# TMP117.net
KiCad netlist of a schematic drawn in EAGLE
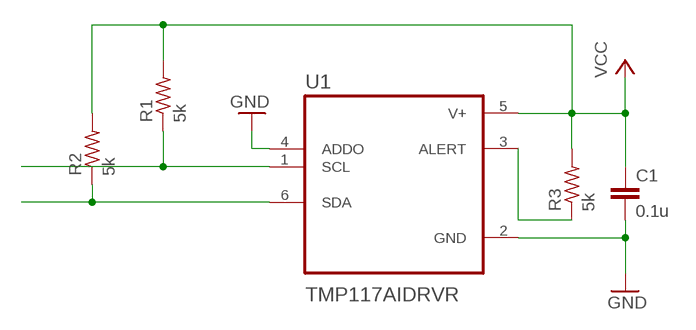
[diagram p0: schematic, sheet 1]

(export (version "E")
  (design (tool "Eeschema 10.0.6"))
  (components
    (comp (ref "C1")
      (value "0.1u")
      (footprint "eagle-import:C0402")
      (libsource (lib "eagle-import") (part "C-EUC0402"))
    )
    (comp (ref "R1")
      (value "5k")
      (footprint "eagle-import:R0402")
      (libsource (lib "eagle-import") (part "R-US_R0402"))
    )
    (comp (ref "R2")
      (value "5k")
      (footprint "eagle-import:R0402")
      (libsource (lib "eagle-import") (part "R-US_R0402"))
    )
    (comp (ref "R3")
      (value "5k")
      (footprint "eagle-import:R0402")
      (libsource (lib "eagle-import") (part "R-US_R0402"))
    )
    (comp (ref "U1")
      (value "TMP117AIDRVR")
      (footprint "eagle-import:SON65P200X200X80-7N")
      (fields (field (name "DIGI-KEY_PART_NUMBER") "296-51834-1-ND") (field (name "MF") "Texas Instruments"))
      (libsource (lib "eagle-import") (part "TMP117AIDRVR"))
    )
  )
  (nets
    (net (code "1") (name "GND") (class "Default")
      (node (ref "C1") (pin "2") (pinfunction "2_2") (pintype "passive"))
      (node (ref "U1") (pin "2") (pinfunction "GND_2") (pintype "power_in"))
      (node (ref "U1") (pin "4") (pinfunction "ADDO_4") (pintype "input"))
    )
    (net (code "2") (name "Net-(U1-ALERT)") (class "Default")
      (node (ref "R3") (pin "1") (pinfunction "1_1") (pintype "passive"))
      (node (ref "U1") (pin "3") (pinfunction "ALERT_3") (pintype "output"))
    )
    (net (code "3") (name "Net-(U1-SCL)") (class "Default")
      (node (ref "R1") (pin "1") (pinfunction "1_1") (pintype "passive"))
      (node (ref "U1") (pin "1") (pinfunction "SCL_1") (pintype "input"))
    )
    (net (code "4") (name "Net-(U1-SDA)") (class "Default")
      (node (ref "R2") (pin "1") (pinfunction "1_1") (pintype "passive"))
      (node (ref "U1") (pin "6") (pinfunction "SDA_6") (pintype "bidirectional"))
    )
    (net (code "5") (name "VCC") (class "Default")
      (node (ref "C1") (pin "1") (pinfunction "1_1") (pintype "passive"))
      (node (ref "R1") (pin "2") (pinfunction "2_2") (pintype "passive"))
      (node (ref "R2") (pin "2") (pinfunction "2_2") (pintype "passive"))
      (node (ref "R3") (pin "2") (pinfunction "2_2") (pintype "passive"))
      (node (ref "U1") (pin "5") (pinfunction "V+_5") (pintype "power_in"))
    )
  )
)
